# evm.net
KiCad netlist of a schematic drawn in EAGLE
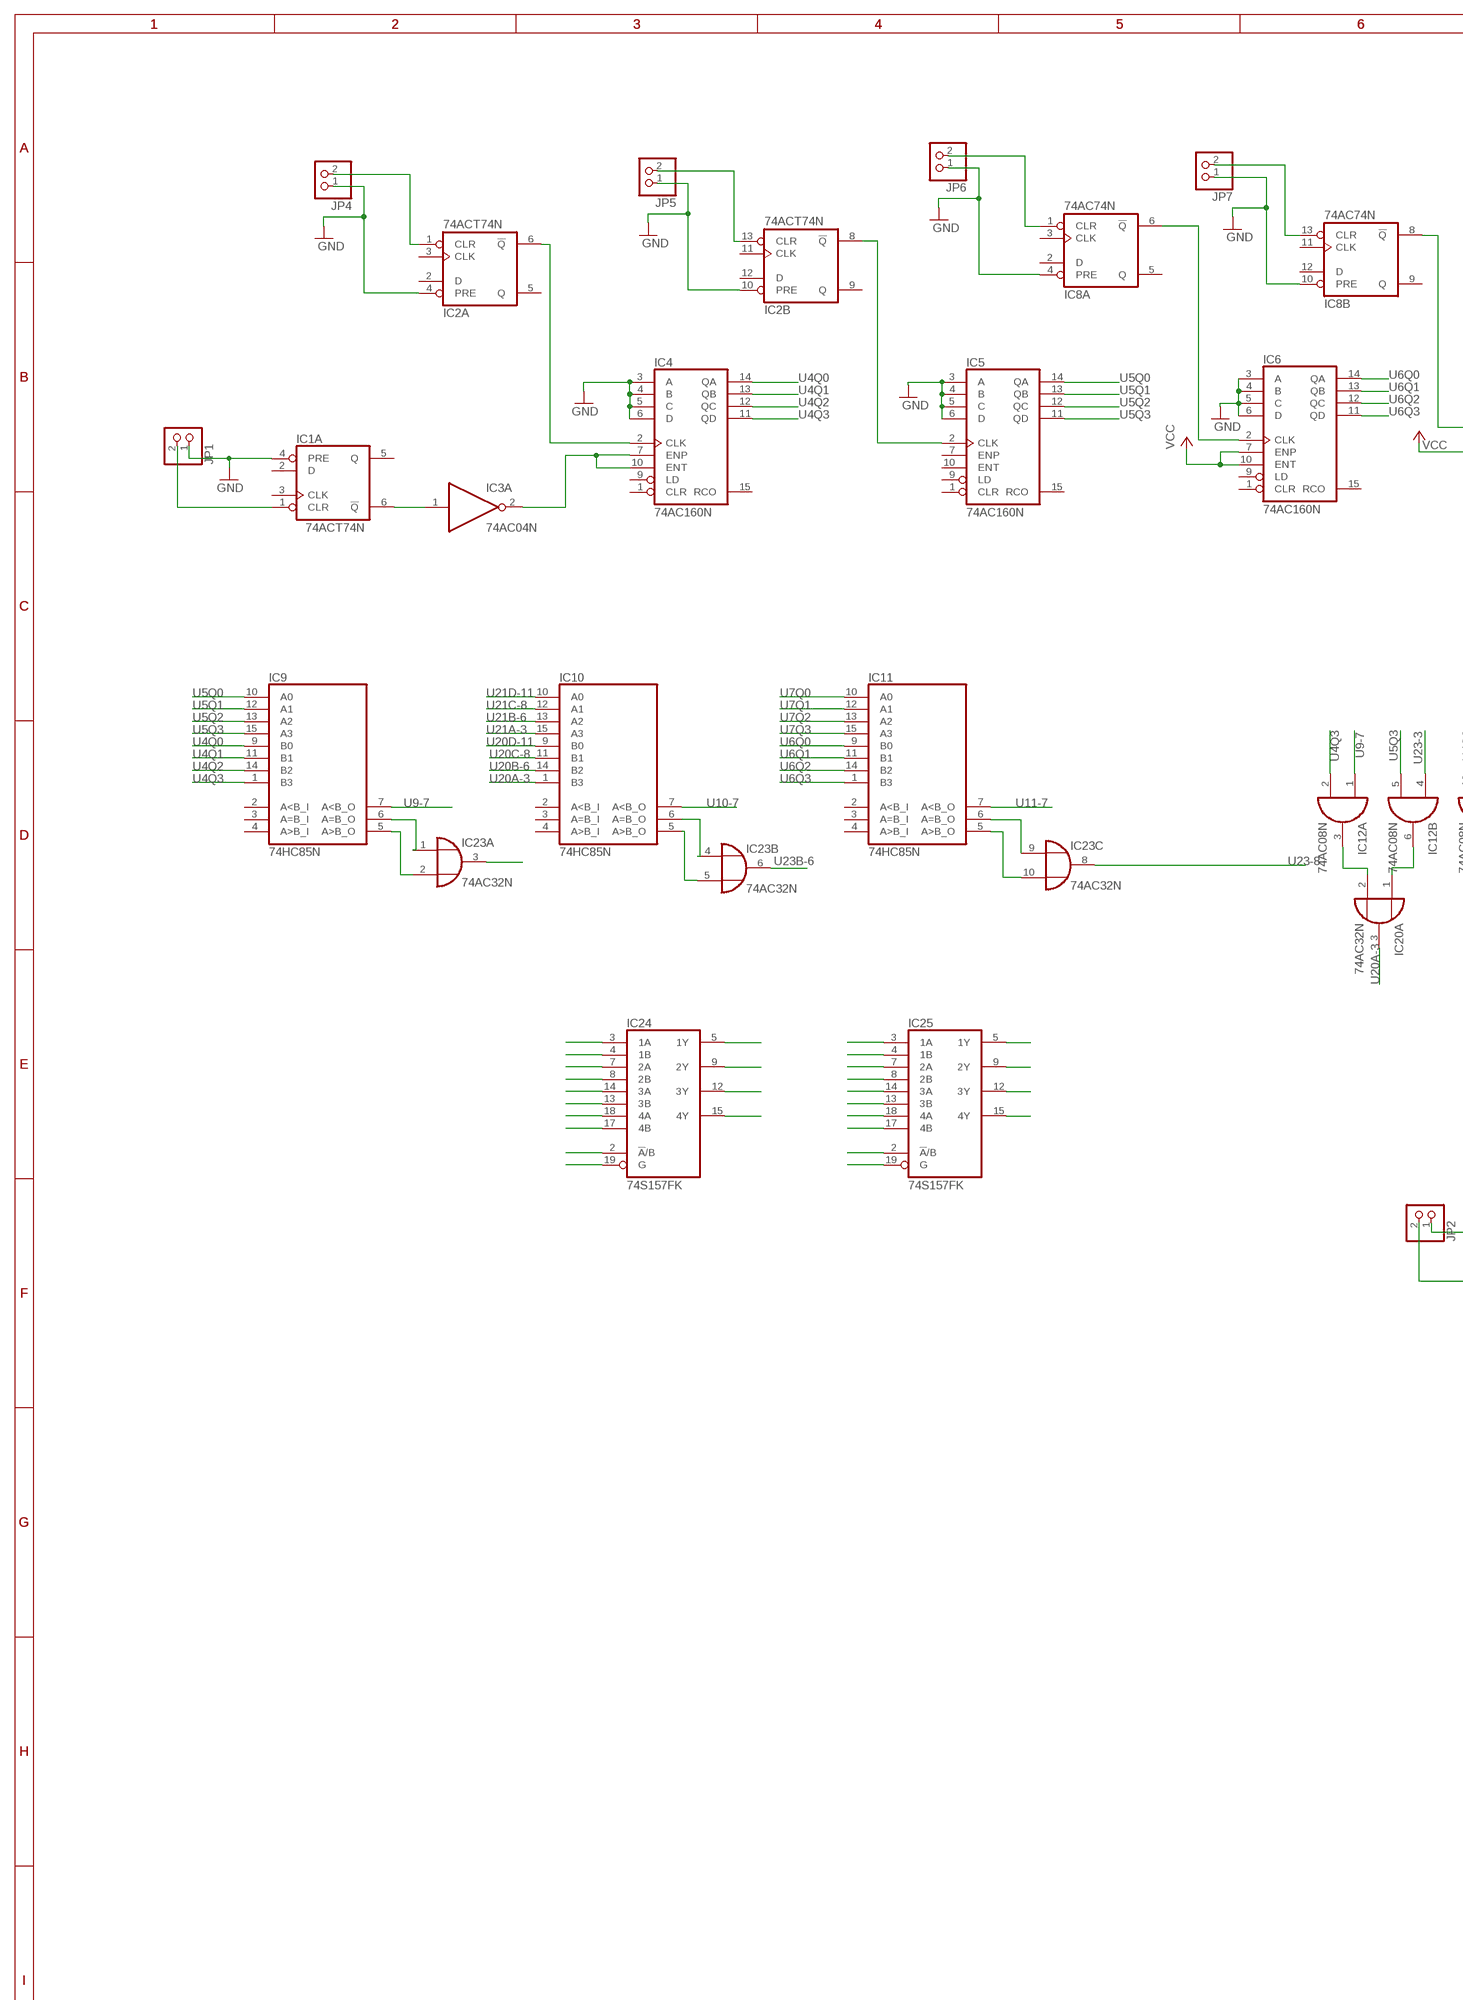
[diagram p0: schematic, sheet 1, part 1 of 2]
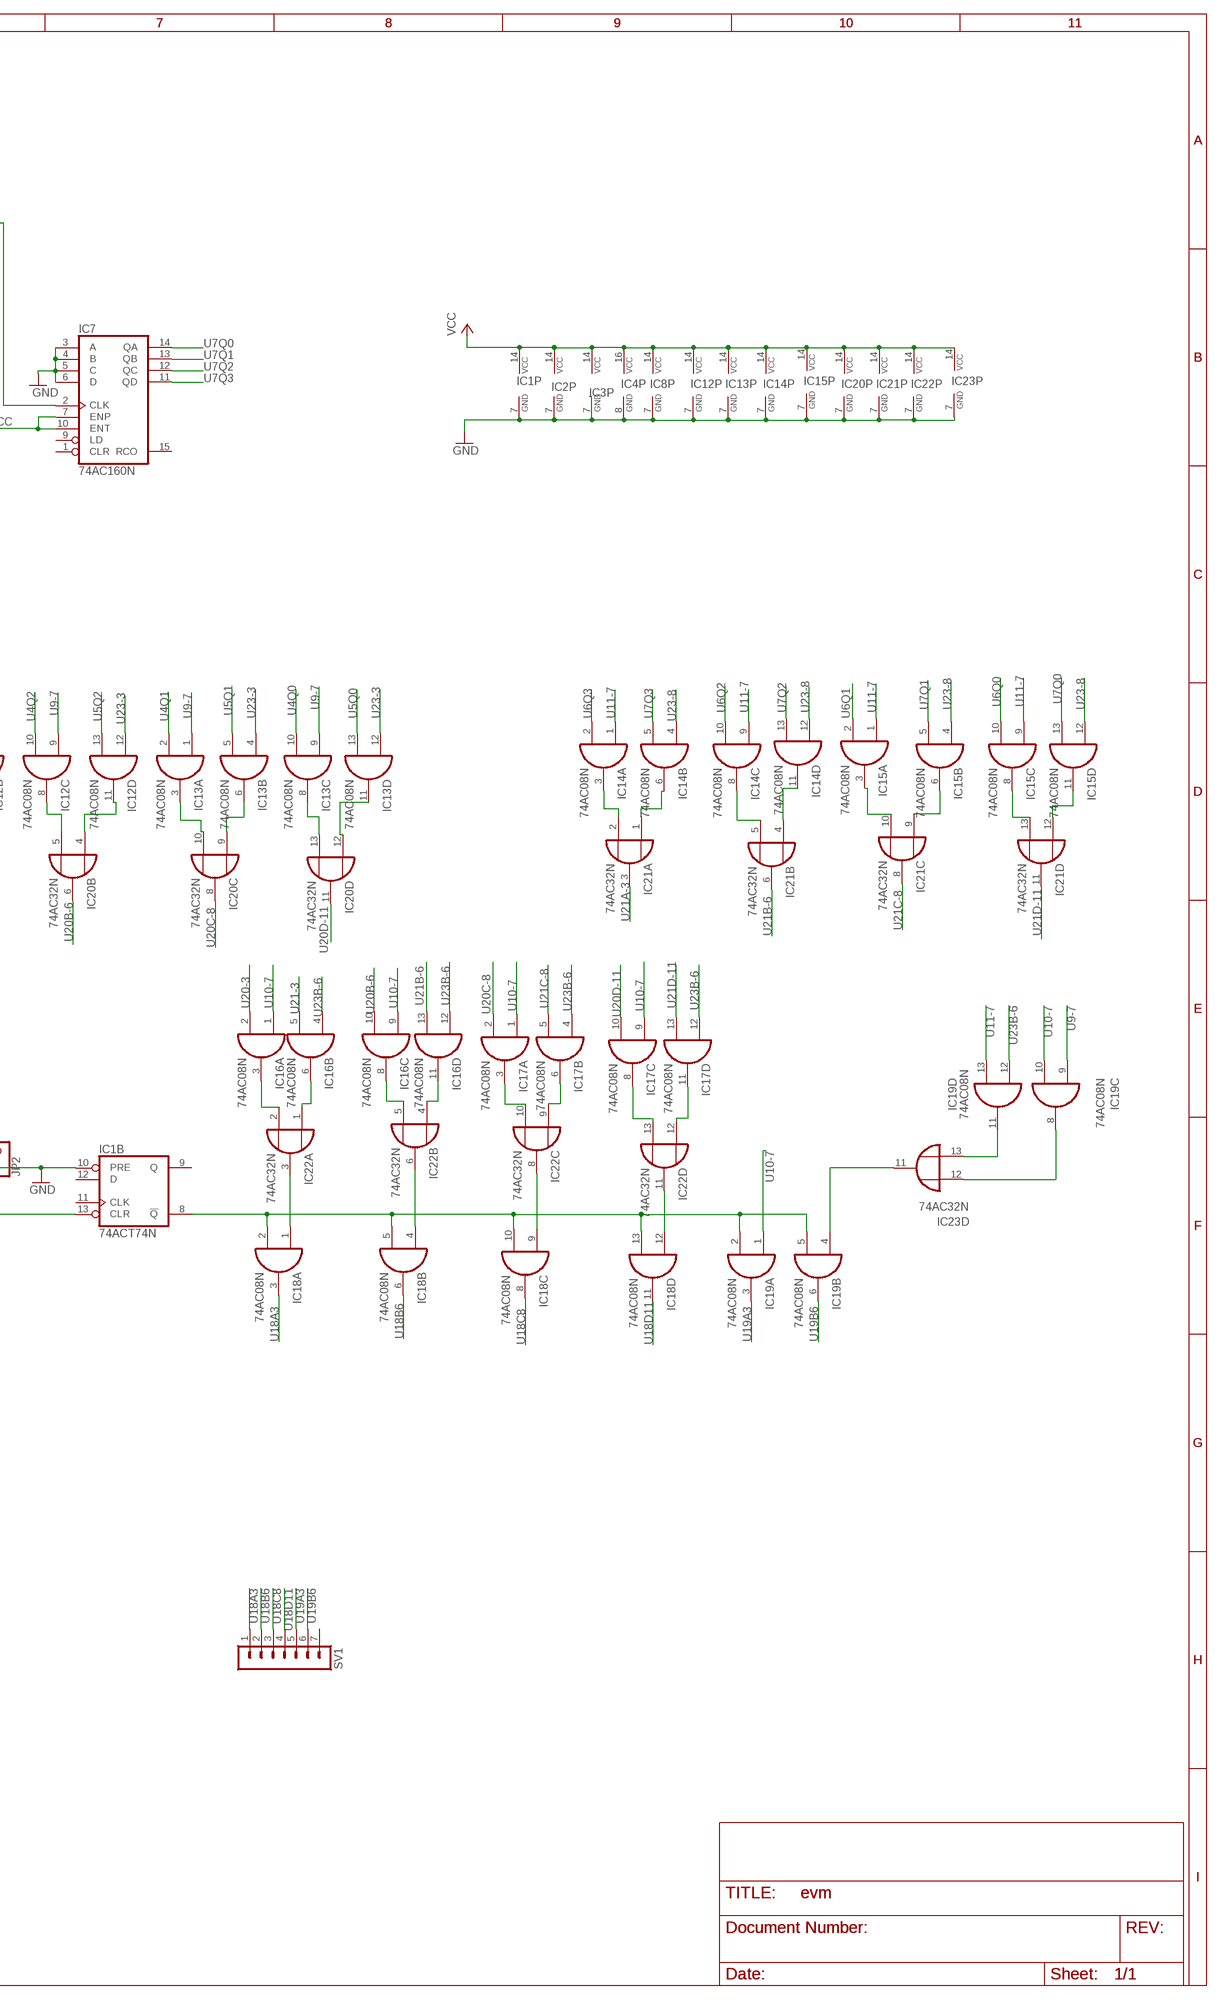
[diagram p1: schematic, sheet 1, part 2 of 2]

(export (version "E")
  (design (tool "Eeschema 10.0.6"))
  (components
    (comp (ref "IC1")
      (value "74ACT74N")
      (footprint "eagle-import:DIL14")
      (libsource (lib "eagle-import") (part "7474NACT"))
    )
    (comp (ref "IC2")
      (value "74ACT74N")
      (footprint "eagle-import:DIL14")
      (libsource (lib "eagle-import") (part "7474NACT"))
    )
    (comp (ref "IC3")
      (value "74AC04N")
      (footprint "eagle-import:DIL14")
      (libsource (lib "eagle-import") (part "7404NAC"))
    )
    (comp (ref "IC4")
      (value "74AC160N")
      (footprint "eagle-import:DIL16")
      (libsource (lib "eagle-import") (part "74160NAC"))
    )
    (comp (ref "IC5")
      (value "74AC160N")
      (footprint "eagle-import:DIL16")
      (libsource (lib "eagle-import") (part "74160NAC"))
    )
    (comp (ref "IC6")
      (value "74AC160N")
      (footprint "eagle-import:DIL16")
      (libsource (lib "eagle-import") (part "74160NAC"))
    )
    (comp (ref "IC7")
      (value "74AC160N")
      (footprint "eagle-import:DIL16")
      (libsource (lib "eagle-import") (part "74160NAC"))
    )
    (comp (ref "IC8")
      (value "74AC74N")
      (footprint "eagle-import:DIL14")
      (libsource (lib "eagle-import") (part "7474NAC"))
    )
    (comp (ref "IC9")
      (value "74HC85N")
      (footprint "eagle-import:DIL16")
      (libsource (lib "eagle-import") (part "7485NHC"))
    )
    (comp (ref "IC10")
      (value "74HC85N")
      (footprint "eagle-import:DIL16")
      (libsource (lib "eagle-import") (part "7485NHC"))
    )
    (comp (ref "IC11")
      (value "74HC85N")
      (footprint "eagle-import:DIL16")
      (libsource (lib "eagle-import") (part "7485NHC"))
    )
    (comp (ref "IC12")
      (value "74AC08N")
      (footprint "eagle-import:DIL14")
      (libsource (lib "eagle-import") (part "7408NAC"))
    )
    (comp (ref "IC13")
      (value "74AC08N")
      (footprint "eagle-import:DIL14")
      (libsource (lib "eagle-import") (part "7408NAC"))
    )
    (comp (ref "IC14")
      (value "74AC08N")
      (footprint "eagle-import:DIL14")
      (libsource (lib "eagle-import") (part "7408NAC"))
    )
    (comp (ref "IC15")
      (value "74AC08N")
      (footprint "eagle-import:DIL14")
      (libsource (lib "eagle-import") (part "7408NAC"))
    )
    (comp (ref "IC16")
      (value "74AC08N")
      (footprint "eagle-import:DIL14")
      (libsource (lib "eagle-import") (part "7408NAC"))
    )
    (comp (ref "IC17")
      (value "74AC08N")
      (footprint "eagle-import:DIL14")
      (libsource (lib "eagle-import") (part "7408NAC"))
    )
    (comp (ref "IC18")
      (value "74AC08N")
      (footprint "eagle-import:DIL14")
      (libsource (lib "eagle-import") (part "7408NAC"))
    )
    (comp (ref "IC19")
      (value "74AC08N")
      (footprint "eagle-import:DIL14")
      (libsource (lib "eagle-import") (part "7408NAC"))
    )
    (comp (ref "IC20")
      (value "74AC32N")
      (footprint "eagle-import:DIL14")
      (libsource (lib "eagle-import") (part "7432NAC"))
    )
    (comp (ref "IC21")
      (value "74AC32N")
      (footprint "eagle-import:DIL14")
      (libsource (lib "eagle-import") (part "7432NAC"))
    )
    (comp (ref "IC22")
      (value "74AC32N")
      (footprint "eagle-import:DIL14")
      (libsource (lib "eagle-import") (part "7432NAC"))
    )
    (comp (ref "IC23")
      (value "74AC32N")
      (footprint "eagle-import:DIL14")
      (libsource (lib "eagle-import") (part "7432NAC"))
    )
    (comp (ref "IC24")
      (value "74S157FK")
      (footprint "eagle-import:LCC20")
      (libsource (lib "eagle-import") (part "74157FKS"))
    )
    (comp (ref "IC25")
      (value "74S157FK")
      (footprint "eagle-import:LCC20")
      (libsource (lib "eagle-import") (part "74157FKS"))
    )
    (comp (ref "JP1")
      (value "PINHD-1X2")
      (footprint "eagle-import:1X02")
      (libsource (lib "eagle-import") (part "PINHD-1X2"))
    )
    (comp (ref "JP2")
      (value "PINHD-1X2")
      (footprint "eagle-import:1X02")
      (libsource (lib "eagle-import") (part "PINHD-1X2"))
    )
    (comp (ref "JP4")
      (value "PINHD-1X2")
      (footprint "eagle-import:1X02")
      (libsource (lib "eagle-import") (part "PINHD-1X2"))
    )
    (comp (ref "JP5")
      (value "PINHD-1X2")
      (footprint "eagle-import:1X02")
      (libsource (lib "eagle-import") (part "PINHD-1X2"))
    )
    (comp (ref "JP6")
      (value "PINHD-1X2")
      (footprint "eagle-import:1X02")
      (libsource (lib "eagle-import") (part "PINHD-1X2"))
    )
    (comp (ref "JP7")
      (value "PINHD-1X2")
      (footprint "eagle-import:1X02")
      (libsource (lib "eagle-import") (part "PINHD-1X2"))
    )
    (comp (ref "SV1")
      (value "MA07-1")
      (footprint "eagle-import:MA07-1")
      (libsource (lib "eagle-import") (part "MA07-1"))
    )
  )
  (nets
    (net (code "1") (name "/U4Q0") (class "Default")
      (node (ref "IC13") (pin "10") (pinfunction "I1_10") (pintype "input"))
      (node (ref "IC4") (pin "14") (pinfunction "QA_14") (pintype "output"))
      (node (ref "IC9") (pin "9") (pinfunction "B0_9") (pintype "input"))
    )
    (net (code "2") (name "/U4Q1") (class "Default")
      (node (ref "IC13") (pin "2") (pinfunction "I1_2") (pintype "input"))
      (node (ref "IC4") (pin "13") (pinfunction "QB_13") (pintype "output"))
      (node (ref "IC9") (pin "11") (pinfunction "B1_11") (pintype "input"))
    )
    (net (code "3") (name "/U4Q2") (class "Default")
      (node (ref "IC12") (pin "10") (pinfunction "I1_10") (pintype "input"))
      (node (ref "IC4") (pin "12") (pinfunction "QC_12") (pintype "output"))
      (node (ref "IC9") (pin "14") (pinfunction "B2_14") (pintype "input"))
    )
    (net (code "4") (name "/U4Q3") (class "Default")
      (node (ref "IC12") (pin "2") (pinfunction "I1_2") (pintype "input"))
      (node (ref "IC4") (pin "11") (pinfunction "QD_11") (pintype "output"))
      (node (ref "IC9") (pin "1") (pinfunction "B3_1") (pintype "input"))
    )
    (net (code "5") (name "/U5Q0") (class "Default")
      (node (ref "IC13") (pin "13") (pinfunction "I1_13") (pintype "input"))
      (node (ref "IC5") (pin "14") (pinfunction "QA_14") (pintype "output"))
      (node (ref "IC9") (pin "10") (pinfunction "A0_10") (pintype "input"))
    )
    (net (code "6") (name "/U5Q1") (class "Default")
      (node (ref "IC13") (pin "5") (pinfunction "I1_5") (pintype "input"))
      (node (ref "IC5") (pin "13") (pinfunction "QB_13") (pintype "output"))
      (node (ref "IC9") (pin "12") (pinfunction "A1_12") (pintype "input"))
    )
    (net (code "7") (name "/U5Q2") (class "Default")
      (node (ref "IC12") (pin "13") (pinfunction "I1_13") (pintype "input"))
      (node (ref "IC5") (pin "12") (pinfunction "QC_12") (pintype "output"))
      (node (ref "IC9") (pin "13") (pinfunction "A2_13") (pintype "input"))
    )
    (net (code "8") (name "/U5Q3") (class "Default")
      (node (ref "IC12") (pin "5") (pinfunction "I1_5") (pintype "input"))
      (node (ref "IC5") (pin "11") (pinfunction "QD_11") (pintype "output"))
      (node (ref "IC9") (pin "15") (pinfunction "A3_15") (pintype "input"))
    )
    (net (code "9") (name "/U6Q0") (class "Default")
      (node (ref "IC11") (pin "9") (pinfunction "B0_9") (pintype "input"))
      (node (ref "IC15") (pin "10") (pinfunction "I1_10") (pintype "input"))
      (node (ref "IC6") (pin "14") (pinfunction "QA_14") (pintype "output"))
    )
    (net (code "10") (name "/U6Q1") (class "Default")
      (node (ref "IC11") (pin "11") (pinfunction "B1_11") (pintype "input"))
      (node (ref "IC15") (pin "2") (pinfunction "I1_2") (pintype "input"))
      (node (ref "IC6") (pin "13") (pinfunction "QB_13") (pintype "output"))
    )
    (net (code "11") (name "/U6Q2") (class "Default")
      (node (ref "IC11") (pin "14") (pinfunction "B2_14") (pintype "input"))
      (node (ref "IC14") (pin "10") (pinfunction "I1_10") (pintype "input"))
      (node (ref "IC6") (pin "12") (pinfunction "QC_12") (pintype "output"))
    )
    (net (code "12") (name "/U6Q3") (class "Default")
      (node (ref "IC11") (pin "1") (pinfunction "B3_1") (pintype "input"))
      (node (ref "IC14") (pin "2") (pinfunction "I1_2") (pintype "input"))
      (node (ref "IC6") (pin "11") (pinfunction "QD_11") (pintype "output"))
    )
    (net (code "13") (name "/U7Q0") (class "Default")
      (node (ref "IC11") (pin "10") (pinfunction "A0_10") (pintype "input"))
      (node (ref "IC15") (pin "13") (pinfunction "I1_13") (pintype "input"))
      (node (ref "IC7") (pin "14") (pinfunction "QA_14") (pintype "output"))
    )
    (net (code "14") (name "/U7Q1") (class "Default")
      (node (ref "IC11") (pin "12") (pinfunction "A1_12") (pintype "input"))
      (node (ref "IC15") (pin "5") (pinfunction "I1_5") (pintype "input"))
      (node (ref "IC7") (pin "13") (pinfunction "QB_13") (pintype "output"))
    )
    (net (code "15") (name "/U7Q2") (class "Default")
      (node (ref "IC11") (pin "13") (pinfunction "A2_13") (pintype "input"))
      (node (ref "IC14") (pin "13") (pinfunction "I1_13") (pintype "input"))
      (node (ref "IC7") (pin "12") (pinfunction "QC_12") (pintype "output"))
    )
    (net (code "16") (name "/U7Q3") (class "Default")
      (node (ref "IC11") (pin "15") (pinfunction "A3_15") (pintype "input"))
      (node (ref "IC14") (pin "5") (pinfunction "I1_5") (pintype "input"))
      (node (ref "IC7") (pin "11") (pinfunction "QD_11") (pintype "output"))
    )
    (net (code "17") (name "/U9-7") (class "Default")
      (node (ref "IC12") (pin "1") (pinfunction "I0_1") (pintype "input"))
      (node (ref "IC12") (pin "9") (pinfunction "I0_9") (pintype "input"))
      (node (ref "IC13") (pin "1") (pinfunction "I0_1") (pintype "input"))
      (node (ref "IC13") (pin "9") (pinfunction "I0_9") (pintype "input"))
      (node (ref "IC19") (pin "9") (pinfunction "I0_9") (pintype "input"))
      (node (ref "IC9") (pin "7") (pinfunction "A<B_O_7") (pintype "output"))
    )
    (net (code "18") (name "/U10-7") (class "Default")
      (node (ref "IC10") (pin "7") (pinfunction "A<B_O_7") (pintype "output"))
      (node (ref "IC16") (pin "1") (pinfunction "I0_1") (pintype "input"))
      (node (ref "IC16") (pin "9") (pinfunction "I0_9") (pintype "input"))
      (node (ref "IC17") (pin "1") (pinfunction "I0_1") (pintype "input"))
      (node (ref "IC17") (pin "9") (pinfunction "I0_9") (pintype "input"))
      (node (ref "IC19") (pin "1") (pinfunction "I0_1") (pintype "input"))
      (node (ref "IC19") (pin "10") (pinfunction "I1_10") (pintype "input"))
    )
    (net (code "19") (name "/U11-7") (class "Default")
      (node (ref "IC11") (pin "7") (pinfunction "A<B_O_7") (pintype "output"))
      (node (ref "IC14") (pin "1") (pinfunction "I0_1") (pintype "input"))
      (node (ref "IC14") (pin "9") (pinfunction "I0_9") (pintype "input"))
      (node (ref "IC15") (pin "1") (pinfunction "I0_1") (pintype "input"))
      (node (ref "IC15") (pin "9") (pinfunction "I0_9") (pintype "input"))
      (node (ref "IC19") (pin "13") (pinfunction "I1_13") (pintype "input"))
    )
    (net (code "20") (name "/U18A3") (class "Default")
      (node (ref "IC18") (pin "3") (pinfunction "O_3") (pintype "output"))
      (node (ref "SV1") (pin "1") (pinfunction "1_1") (pintype "passive"))
    )
    (net (code "21") (name "/U18B6") (class "Default")
      (node (ref "IC18") (pin "6") (pinfunction "O_6") (pintype "output"))
      (node (ref "SV1") (pin "2") (pinfunction "2_2") (pintype "passive"))
    )
    (net (code "22") (name "/U18C8") (class "Default")
      (node (ref "IC18") (pin "8") (pinfunction "O_8") (pintype "output"))
      (node (ref "SV1") (pin "3") (pinfunction "3_3") (pintype "passive"))
    )
    (net (code "23") (name "/U18D11") (class "Default")
      (node (ref "IC18") (pin "11") (pinfunction "O_11") (pintype "output"))
      (node (ref "SV1") (pin "4") (pinfunction "4_4") (pintype "passive"))
    )
    (net (code "24") (name "/U19A3") (class "Default")
      (node (ref "IC19") (pin "3") (pinfunction "O_3") (pintype "output"))
      (node (ref "SV1") (pin "5") (pinfunction "5_5") (pintype "passive"))
    )
    (net (code "25") (name "/U19B6") (class "Default")
      (node (ref "IC19") (pin "6") (pinfunction "O_6") (pintype "output"))
      (node (ref "SV1") (pin "6") (pinfunction "6_6") (pintype "passive"))
    )
    (net (code "26") (name "/U20-3") (class "Default")
      (node (ref "IC16") (pin "2") (pinfunction "I1_2") (pintype "input"))
    )
    (net (code "27") (name "/U20A-3") (class "Default")
      (node (ref "IC10") (pin "1") (pinfunction "B3_1") (pintype "input"))
      (node (ref "IC20") (pin "3") (pinfunction "O_3") (pintype "output"))
    )
    (net (code "28") (name "/U20B-6") (class "Default")
      (node (ref "IC10") (pin "14") (pinfunction "B2_14") (pintype "input"))
      (node (ref "IC16") (pin "10") (pinfunction "I1_10") (pintype "input"))
      (node (ref "IC20") (pin "6") (pinfunction "O_6") (pintype "output"))
    )
    (net (code "29") (name "/U20C-8") (class "Default")
      (node (ref "IC10") (pin "11") (pinfunction "B1_11") (pintype "input"))
      (node (ref "IC17") (pin "2") (pinfunction "I1_2") (pintype "input"))
      (node (ref "IC20") (pin "8") (pinfunction "O_8") (pintype "output"))
    )
    (net (code "30") (name "/U20D-11") (class "Default")
      (node (ref "IC10") (pin "9") (pinfunction "B0_9") (pintype "input"))
      (node (ref "IC17") (pin "10") (pinfunction "I1_10") (pintype "input"))
      (node (ref "IC20") (pin "11") (pinfunction "O_11") (pintype "output"))
    )
    (net (code "31") (name "/U21-3") (class "Default")
      (node (ref "IC16") (pin "5") (pinfunction "I1_5") (pintype "input"))
    )
    (net (code "32") (name "/U21A-3") (class "Default")
      (node (ref "IC10") (pin "15") (pinfunction "A3_15") (pintype "input"))
      (node (ref "IC21") (pin "3") (pinfunction "O_3") (pintype "output"))
    )
    (net (code "33") (name "/U21B-6") (class "Default")
      (node (ref "IC10") (pin "13") (pinfunction "A2_13") (pintype "input"))
      (node (ref "IC16") (pin "13") (pinfunction "I1_13") (pintype "input"))
      (node (ref "IC21") (pin "6") (pinfunction "O_6") (pintype "output"))
    )
    (net (code "34") (name "/U21C-8") (class "Default")
      (node (ref "IC10") (pin "12") (pinfunction "A1_12") (pintype "input"))
      (node (ref "IC17") (pin "5") (pinfunction "I1_5") (pintype "input"))
      (node (ref "IC21") (pin "8") (pinfunction "O_8") (pintype "output"))
    )
    (net (code "35") (name "/U21D-11") (class "Default")
      (node (ref "IC10") (pin "10") (pinfunction "A0_10") (pintype "input"))
      (node (ref "IC17") (pin "13") (pinfunction "I1_13") (pintype "input"))
      (node (ref "IC21") (pin "11") (pinfunction "O_11") (pintype "output"))
    )
    (net (code "36") (name "/U23-3") (class "Default")
      (node (ref "IC12") (pin "12") (pinfunction "I0_12") (pintype "input"))
      (node (ref "IC12") (pin "4") (pinfunction "I0_4") (pintype "input"))
      (node (ref "IC13") (pin "12") (pinfunction "I0_12") (pintype "input"))
      (node (ref "IC13") (pin "4") (pinfunction "I0_4") (pintype "input"))
    )
    (net (code "37") (name "/U23-8") (class "Default")
      (node (ref "IC14") (pin "12") (pinfunction "I0_12") (pintype "input"))
      (node (ref "IC14") (pin "4") (pinfunction "I0_4") (pintype "input"))
      (node (ref "IC15") (pin "12") (pinfunction "I0_12") (pintype "input"))
      (node (ref "IC15") (pin "4") (pinfunction "I0_4") (pintype "input"))
      (node (ref "IC23") (pin "8") (pinfunction "O_8") (pintype "output"))
    )
    (net (code "38") (name "/U23B-6") (class "Default")
      (node (ref "IC16") (pin "12") (pinfunction "I0_12") (pintype "input"))
      (node (ref "IC16") (pin "4") (pinfunction "I0_4") (pintype "input"))
      (node (ref "IC17") (pin "12") (pinfunction "I0_12") (pintype "input"))
      (node (ref "IC17") (pin "4") (pinfunction "I0_4") (pintype "input"))
      (node (ref "IC19") (pin "12") (pinfunction "I0_12") (pintype "input"))
      (node (ref "IC23") (pin "6") (pinfunction "O_6") (pintype "output"))
    )
    (net (code "39") (name "GND") (class "Default")
      (node (ref "IC1") (pin "10") (pinfunction "PRE_10") (pintype "input"))
      (node (ref "IC1") (pin "4") (pinfunction "PRE_4") (pintype "input"))
      (node (ref "IC1") (pin "7") (pinfunction "GND_7") (pintype "power_in"))
      (node (ref "IC12") (pin "7") (pinfunction "GND_7") (pintype "power_in"))
      (node (ref "IC13") (pin "7") (pinfunction "GND_7") (pintype "power_in"))
      (node (ref "IC14") (pin "7") (pinfunction "GND_7") (pintype "power_in"))
      (node (ref "IC15") (pin "7") (pinfunction "GND_7") (pintype "power_in"))
      (node (ref "IC2") (pin "10") (pinfunction "PRE_10") (pintype "input"))
      (node (ref "IC2") (pin "4") (pinfunction "PRE_4") (pintype "input"))
      (node (ref "IC2") (pin "7") (pinfunction "GND_7") (pintype "power_in"))
      (node (ref "IC20") (pin "7") (pinfunction "GND_7") (pintype "power_in"))
      (node (ref "IC21") (pin "7") (pinfunction "GND_7") (pintype "power_in"))
      (node (ref "IC22") (pin "7") (pinfunction "GND_7") (pintype "power_in"))
      (node (ref "IC23") (pin "7") (pinfunction "GND_7") (pintype "power_in"))
      (node (ref "IC3") (pin "7") (pinfunction "GND_7") (pintype "power_in"))
      (node (ref "IC4") (pin "3") (pinfunction "A_3") (pintype "input"))
      (node (ref "IC4") (pin "4") (pinfunction "B_4") (pintype "input"))
      (node (ref "IC4") (pin "5") (pinfunction "C_5") (pintype "input"))
      (node (ref "IC4") (pin "6") (pinfunction "D_6") (pintype "input"))
      (node (ref "IC4") (pin "8") (pinfunction "GND_8") (pintype "power_in"))
      (node (ref "IC5") (pin "3") (pinfunction "A_3") (pintype "input"))
      (node (ref "IC5") (pin "4") (pinfunction "B_4") (pintype "input"))
      (node (ref "IC5") (pin "5") (pinfunction "C_5") (pintype "input"))
      (node (ref "IC5") (pin "6") (pinfunction "D_6") (pintype "input"))
      (node (ref "IC6") (pin "3") (pinfunction "A_3") (pintype "input"))
      (node (ref "IC6") (pin "4") (pinfunction "B_4") (pintype "input"))
      (node (ref "IC6") (pin "5") (pinfunction "C_5") (pintype "input"))
      (node (ref "IC6") (pin "6") (pinfunction "D_6") (pintype "input"))
      (node (ref "IC7") (pin "3") (pinfunction "A_3") (pintype "input"))
      (node (ref "IC7") (pin "4") (pinfunction "B_4") (pintype "input"))
      (node (ref "IC7") (pin "5") (pinfunction "C_5") (pintype "input"))
      (node (ref "IC7") (pin "6") (pinfunction "D_6") (pintype "input"))
      (node (ref "IC8") (pin "10") (pinfunction "PRE_10") (pintype "input"))
      (node (ref "IC8") (pin "4") (pinfunction "PRE_4") (pintype "input"))
      (node (ref "IC8") (pin "7") (pinfunction "GND_7") (pintype "power_in"))
      (node (ref "JP1") (pin "1") (pinfunction "1_1") (pintype "passive"))
      (node (ref "JP2") (pin "1") (pinfunction "1_1") (pintype "passive"))
      (node (ref "JP4") (pin "1") (pinfunction "1_1") (pintype "passive"))
      (node (ref "JP5") (pin "1") (pinfunction "1_1") (pintype "passive"))
      (node (ref "JP6") (pin "1") (pinfunction "1_1") (pintype "passive"))
      (node (ref "JP7") (pin "1") (pinfunction "1_1") (pintype "passive"))
    )
    (net (code "40") (name "Net-(IC1A-CLR)") (class "Default")
      (node (ref "IC1") (pin "1") (pinfunction "CLR_1") (pintype "input"))
      (node (ref "JP1") (pin "2") (pinfunction "2_2") (pintype "passive"))
    )
    (net (code "41") (name "Net-(IC1A-~{Q})") (class "Default")
      (node (ref "IC1") (pin "6") (pinfunction "~{Q}_6") (pintype "output"))
      (node (ref "IC3") (pin "1") (pinfunction "I_1") (pintype "input"))
    )
    (net (code "42") (name "Net-(IC1B-CLR)") (class "Default")
      (node (ref "IC1") (pin "13") (pinfunction "CLR_13") (pintype "input"))
      (node (ref "JP2") (pin "2") (pinfunction "2_2") (pintype "passive"))
    )
    (net (code "43") (name "Net-(IC2A-CLR)") (class "Default")
      (node (ref "IC2") (pin "1") (pinfunction "CLR_1") (pintype "input"))
      (node (ref "JP4") (pin "2") (pinfunction "2_2") (pintype "passive"))
    )
    (net (code "44") (name "Net-(IC2A-~{Q})") (class "Default")
      (node (ref "IC2") (pin "6") (pinfunction "~{Q}_6") (pintype "output"))
      (node (ref "IC4") (pin "2") (pinfunction "CLK_2") (pintype "input"))
    )
    (net (code "45") (name "Net-(IC2B-CLR)") (class "Default")
      (node (ref "IC2") (pin "13") (pinfunction "CLR_13") (pintype "input"))
      (node (ref "JP5") (pin "2") (pinfunction "2_2") (pintype "passive"))
    )
    (net (code "46") (name "Net-(IC2B-~{Q})") (class "Default")
      (node (ref "IC2") (pin "8") (pinfunction "~{Q}_8") (pintype "output"))
      (node (ref "IC5") (pin "2") (pinfunction "CLK_2") (pintype "input"))
    )
    (net (code "47") (name "Net-(IC3A-O)") (class "Default")
      (node (ref "IC3") (pin "2") (pinfunction "O_2") (pintype "output"))
      (node (ref "IC4") (pin "10") (pinfunction "ENT_10") (pintype "input"))
      (node (ref "IC4") (pin "7") (pinfunction "ENP_7") (pintype "input"))
    )
    (net (code "48") (name "Net-(IC6A-CLK)") (class "Default")
      (node (ref "IC6") (pin "2") (pinfunction "CLK_2") (pintype "input"))
      (node (ref "IC8") (pin "6") (pinfunction "~{Q}_6") (pintype "output"))
    )
    (net (code "49") (name "Net-(IC7A-CLK)") (class "Default")
      (node (ref "IC7") (pin "2") (pinfunction "CLK_2") (pintype "input"))
      (node (ref "IC8") (pin "8") (pinfunction "~{Q}_8") (pintype "output"))
    )
    (net (code "50") (name "Net-(IC7A-ENP)") (class "Default")
      (node (ref "IC7") (pin "10") (pinfunction "ENT_10") (pintype "input"))
      (node (ref "IC7") (pin "7") (pinfunction "ENP_7") (pintype "input"))
    )
    (net (code "51") (name "Net-(IC8A-CLR)") (class "Default")
      (node (ref "IC8") (pin "1") (pinfunction "CLR_1") (pintype "input"))
      (node (ref "JP6") (pin "2") (pinfunction "2_2") (pintype "passive"))
    )
    (net (code "52") (name "Net-(IC8B-CLR)") (class "Default")
      (node (ref "IC8") (pin "13") (pinfunction "CLR_13") (pintype "input"))
      (node (ref "JP7") (pin "2") (pinfunction "2_2") (pintype "passive"))
    )
    (net (code "53") (name "Net-(IC10A-A=B_O)") (class "Default")
      (node (ref "IC10") (pin "6") (pinfunction "A=B_O_6") (pintype "output"))
      (node (ref "IC23") (pin "4") (pinfunction "I0_4") (pintype "input"))
    )
    (net (code "54") (name "Net-(IC10A-A>B_O)") (class "Default")
      (node (ref "IC10") (pin "5") (pinfunction "A>B_O_5") (pintype "output"))
      (node (ref "IC23") (pin "5") (pinfunction "I1_5") (pintype "input"))
    )
    (net (code "55") (name "Net-(IC11A-A=B_O)") (class "Default")
      (node (ref "IC11") (pin "6") (pinfunction "A=B_O_6") (pintype "output"))
      (node (ref "IC23") (pin "9") (pinfunction "I0_9") (pintype "input"))
    )
    (net (code "56") (name "Net-(IC11A-A>B_O)") (class "Default")
      (node (ref "IC11") (pin "5") (pinfunction "A>B_O_5") (pintype "output"))
      (node (ref "IC23") (pin "10") (pinfunction "I1_10") (pintype "input"))
    )
    (net (code "57") (name "Net-(IC12A-O)") (class "Default")
      (node (ref "IC12") (pin "3") (pinfunction "O_3") (pintype "output"))
      (node (ref "IC20") (pin "2") (pinfunction "I1_2") (pintype "input"))
    )
    (net (code "58") (name "Net-(IC12B-O)") (class "Default")
      (node (ref "IC12") (pin "6") (pinfunction "O_6") (pintype "output"))
      (node (ref "IC20") (pin "1") (pinfunction "I0_1") (pintype "input"))
    )
    (net (code "59") (name "Net-(IC12C-O)") (class "Default")
      (node (ref "IC12") (pin "8") (pinfunction "O_8") (pintype "output"))
      (node (ref "IC20") (pin "5") (pinfunction "I1_5") (pintype "input"))
    )
    (net (code "60") (name "Net-(IC12D-O)") (class "Default")
      (node (ref "IC12") (pin "11") (pinfunction "O_11") (pintype "output"))
      (node (ref "IC20") (pin "4") (pinfunction "I0_4") (pintype "input"))
    )
    (net (code "61") (name "Net-(IC13A-O)") (class "Default")
      (node (ref "IC13") (pin "3") (pinfunction "O_3") (pintype "output"))
      (node (ref "IC20") (pin "10") (pinfunction "I1_10") (pintype "input"))
    )
    (net (code "62") (name "Net-(IC13B-O)") (class "Default")
      (node (ref "IC13") (pin "6") (pinfunction "O_6") (pintype "output"))
      (node (ref "IC20") (pin "9") (pinfunction "I0_9") (pintype "input"))
    )
    (net (code "63") (name "Net-(IC13C-O)") (class "Default")
      (node (ref "IC13") (pin "8") (pinfunction "O_8") (pintype "output"))
      (node (ref "IC20") (pin "13") (pinfunction "I1_13") (pintype "input"))
    )
    (net (code "64") (name "Net-(IC13D-O)") (class "Default")
      (node (ref "IC13") (pin "11") (pinfunction "O_11") (pintype "output"))
      (node (ref "IC20") (pin "12") (pinfunction "I0_12") (pintype "input"))
    )
    (net (code "65") (name "Net-(IC14A-O)") (class "Default")
      (node (ref "IC14") (pin "3") (pinfunction "O_3") (pintype "output"))
      (node (ref "IC21") (pin "2") (pinfunction "I1_2") (pintype "input"))
    )
    (net (code "66") (name "Net-(IC14B-O)") (class "Default")
      (node (ref "IC14") (pin "6") (pinfunction "O_6") (pintype "output"))
      (node (ref "IC21") (pin "1") (pinfunction "I0_1") (pintype "input"))
    )
    (net (code "67") (name "Net-(IC14C-O)") (class "Default")
      (node (ref "IC14") (pin "8") (pinfunction "O_8") (pintype "output"))
      (node (ref "IC21") (pin "5") (pinfunction "I1_5") (pintype "input"))
    )
    (net (code "68") (name "Net-(IC14D-O)") (class "Default")
      (node (ref "IC14") (pin "11") (pinfunction "O_11") (pintype "output"))
      (node (ref "IC21") (pin "4") (pinfunction "I0_4") (pintype "input"))
    )
    (net (code "69") (name "Net-(IC15A-O)") (class "Default")
      (node (ref "IC15") (pin "3") (pinfunction "O_3") (pintype "output"))
      (node (ref "IC21") (pin "10") (pinfunction "I1_10") (pintype "input"))
    )
    (net (code "70") (name "Net-(IC15B-O)") (class "Default")
      (node (ref "IC15") (pin "6") (pinfunction "O_6") (pintype "output"))
      (node (ref "IC21") (pin "9") (pinfunction "I0_9") (pintype "input"))
    )
    (net (code "71") (name "Net-(IC15C-O)") (class "Default")
      (node (ref "IC15") (pin "8") (pinfunction "O_8") (pintype "output"))
      (node (ref "IC21") (pin "13") (pinfunction "I1_13") (pintype "input"))
    )
    (net (code "72") (name "Net-(IC15D-O)") (class "Default")
      (node (ref "IC15") (pin "11") (pinfunction "O_11") (pintype "output"))
      (node (ref "IC21") (pin "12") (pinfunction "I0_12") (pintype "input"))
    )
    (net (code "73") (name "Net-(IC16A-O)") (class "Default")
      (node (ref "IC16") (pin "3") (pinfunction "O_3") (pintype "output"))
      (node (ref "IC22") (pin "2") (pinfunction "I1_2") (pintype "input"))
    )
    (net (code "74") (name "Net-(IC16B-O)") (class "Default")
      (node (ref "IC16") (pin "6") (pinfunction "O_6") (pintype "output"))
      (node (ref "IC22") (pin "1") (pinfunction "I0_1") (pintype "input"))
    )
    (net (code "75") (name "Net-(IC16C-O)") (class "Default")
      (node (ref "IC16") (pin "8") (pinfunction "O_8") (pintype "output"))
      (node (ref "IC22") (pin "5") (pinfunction "I1_5") (pintype "input"))
    )
    (net (code "76") (name "Net-(IC16D-O)") (class "Default")
      (node (ref "IC16") (pin "11") (pinfunction "O_11") (pintype "output"))
      (node (ref "IC22") (pin "4") (pinfunction "I0_4") (pintype "input"))
    )
    (net (code "77") (name "Net-(IC17A-O)") (class "Default")
      (node (ref "IC17") (pin "3") (pinfunction "O_3") (pintype "output"))
      (node (ref "IC22") (pin "10") (pinfunction "I1_10") (pintype "input"))
    )
    (net (code "78") (name "Net-(IC17B-O)") (class "Default")
      (node (ref "IC17") (pin "6") (pinfunction "O_6") (pintype "output"))
      (node (ref "IC22") (pin "9") (pinfunction "I0_9") (pintype "input"))
    )
    (net (code "79") (name "Net-(IC17C-O)") (class "Default")
      (node (ref "IC17") (pin "8") (pinfunction "O_8") (pintype "output"))
      (node (ref "IC22") (pin "13") (pinfunction "I1_13") (pintype "input"))
    )
    (net (code "80") (name "Net-(IC17D-O)") (class "Default")
      (node (ref "IC17") (pin "11") (pinfunction "O_11") (pintype "output"))
      (node (ref "IC22") (pin "12") (pinfunction "I0_12") (pintype "input"))
    )
    (net (code "81") (name "Net-(IC18A-I0)") (class "Default")
      (node (ref "IC18") (pin "1") (pinfunction "I0_1") (pintype "input"))
      (node (ref "IC22") (pin "3") (pinfunction "O_3") (pintype "output"))
    )
    (net (code "82") (name "Net-(IC18A-I1)") (class "Default")
      (node (ref "IC1") (pin "8") (pinfunction "~{Q}_8") (pintype "output"))
      (node (ref "IC18") (pin "10") (pinfunction "I1_10") (pintype "input"))
      (node (ref "IC18") (pin "13") (pinfunction "I1_13") (pintype "input"))
      (node (ref "IC18") (pin "2") (pinfunction "I1_2") (pintype "input"))
      (node (ref "IC18") (pin "5") (pinfunction "I1_5") (pintype "input"))
      (node (ref "IC19") (pin "2") (pinfunction "I1_2") (pintype "input"))
      (node (ref "IC19") (pin "5") (pinfunction "I1_5") (pintype "input"))
    )
    (net (code "83") (name "Net-(IC18B-I0)") (class "Default")
      (node (ref "IC18") (pin "4") (pinfunction "I0_4") (pintype "input"))
      (node (ref "IC22") (pin "6") (pinfunction "O_6") (pintype "output"))
    )
    (net (code "84") (name "Net-(IC18C-I0)") (class "Default")
      (node (ref "IC18") (pin "9") (pinfunction "I0_9") (pintype "input"))
      (node (ref "IC22") (pin "8") (pinfunction "O_8") (pintype "output"))
    )
    (net (code "85") (name "Net-(IC18D-I0)") (class "Default")
      (node (ref "IC18") (pin "12") (pinfunction "I0_12") (pintype "input"))
      (node (ref "IC22") (pin "11") (pinfunction "O_11") (pintype "output"))
    )
    (net (code "86") (name "Net-(IC19B-I0)") (class "Default")
      (node (ref "IC19") (pin "4") (pinfunction "I0_4") (pintype "input"))
      (node (ref "IC23") (pin "11") (pinfunction "O_11") (pintype "output"))
    )
    (net (code "87") (name "Net-(IC19C-O)") (class "Default")
      (node (ref "IC19") (pin "8") (pinfunction "O_8") (pintype "output"))
      (node (ref "IC23") (pin "12") (pinfunction "I0_12") (pintype "input"))
    )
    (net (code "88") (name "Net-(IC19D-O)") (class "Default")
      (node (ref "IC19") (pin "11") (pinfunction "O_11") (pintype "output"))
      (node (ref "IC23") (pin "13") (pinfunction "I1_13") (pintype "input"))
    )
    (net (code "89") (name "Net-(IC23A-I0)") (class "Default")
      (node (ref "IC23") (pin "1") (pinfunction "I0_1") (pintype "input"))
      (node (ref "IC9") (pin "6") (pinfunction "A=B_O_6") (pintype "output"))
    )
    (net (code "90") (name "Net-(IC23A-I1)") (class "Default")
      (node (ref "IC23") (pin "2") (pinfunction "I1_2") (pintype "input"))
      (node (ref "IC9") (pin "5") (pinfunction "A>B_O_5") (pintype "output"))
    )
    (net (code "91") (name "VCC") (class "Default")
      (node (ref "IC1") (pin "14") (pinfunction "VCC_14") (pintype "power_in"))
      (node (ref "IC12") (pin "14") (pinfunction "VCC_14") (pintype "power_in"))
      (node (ref "IC13") (pin "14") (pinfunction "VCC_14") (pintype "power_in"))
      (node (ref "IC14") (pin "14") (pinfunction "VCC_14") (pintype "power_in"))
      (node (ref "IC15") (pin "14") (pinfunction "VCC_14") (pintype "power_in"))
      (node (ref "IC2") (pin "14") (pinfunction "VCC_14") (pintype "power_in"))
      (node (ref "IC20") (pin "14") (pinfunction "VCC_14") (pintype "power_in"))
      (node (ref "IC21") (pin "14") (pinfunction "VCC_14") (pintype "power_in"))
      (node (ref "IC22") (pin "14") (pinfunction "VCC_14") (pintype "power_in"))
      (node (ref "IC23") (pin "14") (pinfunction "VCC_14") (pintype "power_in"))
      (node (ref "IC3") (pin "14") (pinfunction "VCC_14") (pintype "power_in"))
      (node (ref "IC4") (pin "16") (pinfunction "VCC_16") (pintype "power_in"))
      (node (ref "IC6") (pin "10") (pinfunction "ENT_10") (pintype "input"))
      (node (ref "IC6") (pin "7") (pinfunction "ENP_7") (pintype "input"))
      (node (ref "IC8") (pin "14") (pinfunction "VCC_14") (pintype "power_in"))
    )
    (net (code "92") (name "unconnected-(IC1A-CLK-Pad3)") (class "Default")
      (node (ref "IC1") (pin "3") (pinfunction "CLK_3") (pintype "input"))
    )
    (net (code "93") (name "unconnected-(IC1A-D-Pad2)") (class "Default")
      (node (ref "IC1") (pin "2") (pinfunction "D_2") (pintype "input"))
    )
    (net (code "94") (name "unconnected-(IC1A-Q-Pad5)") (class "Default")
      (node (ref "IC1") (pin "5") (pinfunction "Q_5") (pintype "output"))
    )
    (net (code "95") (name "unconnected-(IC1B-CLK-Pad11)") (class "Default")
      (node (ref "IC1") (pin "11") (pinfunction "CLK_11") (pintype "input"))
    )
    (net (code "96") (name "unconnected-(IC1B-D-Pad12)") (class "Default")
      (node (ref "IC1") (pin "12") (pinfunction "D_12") (pintype "input"))
    )
    (net (code "97") (name "unconnected-(IC1B-Q-Pad9)") (class "Default")
      (node (ref "IC1") (pin "9") (pinfunction "Q_9") (pintype "output"))
    )
    (net (code "98") (name "unconnected-(IC2A-CLK-Pad3)") (class "Default")
      (node (ref "IC2") (pin "3") (pinfunction "CLK_3") (pintype "input"))
    )
    (net (code "99") (name "unconnected-(IC2A-D-Pad2)") (class "Default")
      (node (ref "IC2") (pin "2") (pinfunction "D_2") (pintype "input"))
    )
    (net (code "100") (name "unconnected-(IC2A-Q-Pad5)") (class "Default")
      (node (ref "IC2") (pin "5") (pinfunction "Q_5") (pintype "output"))
    )
    (net (code "101") (name "unconnected-(IC2B-CLK-Pad11)") (class "Default")
      (node (ref "IC2") (pin "11") (pinfunction "CLK_11") (pintype "input"))
    )
    (net (code "102") (name "unconnected-(IC2B-D-Pad12)") (class "Default")
      (node (ref "IC2") (pin "12") (pinfunction "D_12") (pintype "input"))
    )
    (net (code "103") (name "unconnected-(IC2B-Q-Pad9)") (class "Default")
      (node (ref "IC2") (pin "9") (pinfunction "Q_9") (pintype "output"))
    )
    (net (code "104") (name "unconnected-(IC4A-CLR-Pad1)") (class "Default")
      (node (ref "IC4") (pin "1") (pinfunction "CLR_1") (pintype "input"))
    )
    (net (code "105") (name "unconnected-(IC4A-LD-Pad9)") (class "Default")
      (node (ref "IC4") (pin "9") (pinfunction "LD_9") (pintype "input"))
    )
    (net (code "106") (name "unconnected-(IC4A-RCO-Pad15)") (class "Default")
      (node (ref "IC4") (pin "15") (pinfunction "RCO_15") (pintype "output"))
    )
    (net (code "107") (name "unconnected-(IC5A-CLR-Pad1)") (class "Default")
      (node (ref "IC5") (pin "1") (pinfunction "CLR_1") (pintype "input"))
    )
    (net (code "108") (name "unconnected-(IC5A-ENP-Pad7)") (class "Default")
      (node (ref "IC5") (pin "7") (pinfunction "ENP_7") (pintype "input"))
    )
    (net (code "109") (name "unconnected-(IC5A-ENT-Pad10)") (class "Default")
      (node (ref "IC5") (pin "10") (pinfunction "ENT_10") (pintype "input"))
    )
    (net (code "110") (name "unconnected-(IC5A-LD-Pad9)") (class "Default")
      (node (ref "IC5") (pin "9") (pinfunction "LD_9") (pintype "input"))
    )
    (net (code "111") (name "unconnected-(IC5A-RCO-Pad15)") (class "Default")
      (node (ref "IC5") (pin "15") (pinfunction "RCO_15") (pintype "output"))
    )
    (net (code "112") (name "unconnected-(IC6A-CLR-Pad1)") (class "Default")
      (node (ref "IC6") (pin "1") (pinfunction "CLR_1") (pintype "input"))
    )
    (net (code "113") (name "unconnected-(IC6A-LD-Pad9)") (class "Default")
      (node (ref "IC6") (pin "9") (pinfunction "LD_9") (pintype "input"))
    )
    (net (code "114") (name "unconnected-(IC6A-RCO-Pad15)") (class "Default")
      (node (ref "IC6") (pin "15") (pinfunction "RCO_15") (pintype "output"))
    )
    (net (code "115") (name "unconnected-(IC7A-CLR-Pad1)") (class "Default")
      (node (ref "IC7") (pin "1") (pinfunction "CLR_1") (pintype "input"))
    )
    (net (code "116") (name "unconnected-(IC7A-LD-Pad9)") (class "Default")
      (node (ref "IC7") (pin "9") (pinfunction "LD_9") (pintype "input"))
    )
    (net (code "117") (name "unconnected-(IC7A-RCO-Pad15)") (class "Default")
      (node (ref "IC7") (pin "15") (pinfunction "RCO_15") (pintype "output"))
    )
    (net (code "118") (name "unconnected-(IC8A-CLK-Pad3)") (class "Default")
      (node (ref "IC8") (pin "3") (pinfunction "CLK_3") (pintype "input"))
    )
    (net (code "119") (name "unconnected-(IC8A-D-Pad2)") (class "Default")
      (node (ref "IC8") (pin "2") (pinfunction "D_2") (pintype "input"))
    )
    (net (code "120") (name "unconnected-(IC8A-Q-Pad5)") (class "Default")
      (node (ref "IC8") (pin "5") (pinfunction "Q_5") (pintype "output"))
    )
    (net (code "121") (name "unconnected-(IC8B-CLK-Pad11)") (class "Default")
      (node (ref "IC8") (pin "11") (pinfunction "CLK_11") (pintype "input"))
    )
    (net (code "122") (name "unconnected-(IC8B-D-Pad12)") (class "Default")
      (node (ref "IC8") (pin "12") (pinfunction "D_12") (pintype "input"))
    )
    (net (code "123") (name "unconnected-(IC8B-Q-Pad9)") (class "Default")
      (node (ref "IC8") (pin "9") (pinfunction "Q_9") (pintype "output"))
    )
    (net (code "124") (name "unconnected-(IC9A-A<B_I-Pad2)") (class "Default")
      (node (ref "IC9") (pin "2") (pinfunction "A<B_I_2") (pintype "input"))
    )
    (net (code "125") (name "unconnected-(IC9A-A=B_I-Pad3)") (class "Default")
      (node (ref "IC9") (pin "3") (pinfunction "A=B_I_3") (pintype "input"))
    )
    (net (code "126") (name "unconnected-(IC9A-A>B_I-Pad4)") (class "Default")
      (node (ref "IC9") (pin "4") (pinfunction "A>B_I_4") (pintype "input"))
    )
    (net (code "127") (name "unconnected-(IC10A-A<B_I-Pad2)") (class "Default")
      (node (ref "IC10") (pin "2") (pinfunction "A<B_I_2") (pintype "input"))
    )
    (net (code "128") (name "unconnected-(IC10A-A=B_I-Pad3)") (class "Default")
      (node (ref "IC10") (pin "3") (pinfunction "A=B_I_3") (pintype "input"))
    )
    (net (code "129") (name "unconnected-(IC10A-A>B_I-Pad4)") (class "Default")
      (node (ref "IC10") (pin "4") (pinfunction "A>B_I_4") (pintype "input"))
    )
    (net (code "130") (name "unconnected-(IC11A-A<B_I-Pad2)") (class "Default")
      (node (ref "IC11") (pin "2") (pinfunction "A<B_I_2") (pintype "input"))
    )
    (net (code "131") (name "unconnected-(IC11A-A=B_I-Pad3)") (class "Default")
      (node (ref "IC11") (pin "3") (pinfunction "A=B_I_3") (pintype "input"))
    )
    (net (code "132") (name "unconnected-(IC11A-A>B_I-Pad4)") (class "Default")
      (node (ref "IC11") (pin "4") (pinfunction "A>B_I_4") (pintype "input"))
    )
    (net (code "133") (name "unconnected-(IC23A-O-Pad3)") (class "Default")
      (node (ref "IC23") (pin "3") (pinfunction "O_3") (pintype "output"))
    )
    (net (code "134") (name "unconnected-(IC24A-1A-Pad3)") (class "Default")
      (node (ref "IC24") (pin "3") (pinfunction "1A_3") (pintype "input"))
    )
    (net (code "135") (name "unconnected-(IC24A-1B-Pad4)") (class "Default")
      (node (ref "IC24") (pin "4") (pinfunction "1B_4") (pintype "input"))
    )
    (net (code "136") (name "unconnected-(IC24A-1Y-Pad5)") (class "Default")
      (node (ref "IC24") (pin "5") (pinfunction "1Y_5") (pintype "output"))
    )
    (net (code "137") (name "unconnected-(IC24A-2A-Pad7)") (class "Default")
      (node (ref "IC24") (pin "7") (pinfunction "2A_7") (pintype "input"))
    )
    (net (code "138") (name "unconnected-(IC24A-2B-Pad8)") (class "Default")
      (node (ref "IC24") (pin "8") (pinfunction "2B_8") (pintype "input"))
    )
    (net (code "139") (name "unconnected-(IC24A-2Y-Pad9)") (class "Default")
      (node (ref "IC24") (pin "9") (pinfunction "2Y_9") (pintype "output"))
    )
    (net (code "140") (name "unconnected-(IC24A-3A-Pad14)") (class "Default")
      (node (ref "IC24") (pin "14") (pinfunction "3A_14") (pintype "input"))
    )
    (net (code "141") (name "unconnected-(IC24A-3B-Pad13)") (class "Default")
      (node (ref "IC24") (pin "13") (pinfunction "3B_13") (pintype "input"))
    )
    (net (code "142") (name "unconnected-(IC24A-3Y-Pad12)") (class "Default")
      (node (ref "IC24") (pin "12") (pinfunction "3Y_12") (pintype "output"))
    )
    (net (code "143") (name "unconnected-(IC24A-4A-Pad18)") (class "Default")
      (node (ref "IC24") (pin "18") (pinfunction "4A_18") (pintype "input"))
    )
    (net (code "144") (name "unconnected-(IC24A-4B-Pad17)") (class "Default")
      (node (ref "IC24") (pin "17") (pinfunction "4B_17") (pintype "input"))
    )
    (net (code "145") (name "unconnected-(IC24A-4Y-Pad15)") (class "Default")
      (node (ref "IC24") (pin "15") (pinfunction "4Y_15") (pintype "output"))
    )
    (net (code "146") (name "unconnected-(IC24A-G-Pad19)") (class "Default")
      (node (ref "IC24") (pin "19") (pinfunction "G_19") (pintype "input"))
    )
    (net (code "147") (name "unconnected-(IC24A-~{A}{slash}B-Pad2)") (class "Default")
      (node (ref "IC24") (pin "2") (pinfunction "~{A}/B_2") (pintype "input"))
    )
    (net (code "148") (name "unconnected-(IC25A-1A-Pad3)") (class "Default")
      (node (ref "IC25") (pin "3") (pinfunction "1A_3") (pintype "input"))
    )
    (net (code "149") (name "unconnected-(IC25A-1B-Pad4)") (class "Default")
      (node (ref "IC25") (pin "4") (pinfunction "1B_4") (pintype "input"))
    )
    (net (code "150") (name "unconnected-(IC25A-1Y-Pad5)") (class "Default")
      (node (ref "IC25") (pin "5") (pinfunction "1Y_5") (pintype "output"))
    )
    (net (code "151") (name "unconnected-(IC25A-2A-Pad7)") (class "Default")
      (node (ref "IC25") (pin "7") (pinfunction "2A_7") (pintype "input"))
    )
    (net (code "152") (name "unconnected-(IC25A-2B-Pad8)") (class "Default")
      (node (ref "IC25") (pin "8") (pinfunction "2B_8") (pintype "input"))
    )
    (net (code "153") (name "unconnected-(IC25A-2Y-Pad9)") (class "Default")
      (node (ref "IC25") (pin "9") (pinfunction "2Y_9") (pintype "output"))
    )
    (net (code "154") (name "unconnected-(IC25A-3A-Pad14)") (class "Default")
      (node (ref "IC25") (pin "14") (pinfunction "3A_14") (pintype "input"))
    )
    (net (code "155") (name "unconnected-(IC25A-3B-Pad13)") (class "Default")
      (node (ref "IC25") (pin "13") (pinfunction "3B_13") (pintype "input"))
    )
    (net (code "156") (name "unconnected-(IC25A-3Y-Pad12)") (class "Default")
      (node (ref "IC25") (pin "12") (pinfunction "3Y_12") (pintype "output"))
    )
    (net (code "157") (name "unconnected-(IC25A-4A-Pad18)") (class "Default")
      (node (ref "IC25") (pin "18") (pinfunction "4A_18") (pintype "input"))
    )
    (net (code "158") (name "unconnected-(IC25A-4B-Pad17)") (class "Default")
      (node (ref "IC25") (pin "17") (pinfunction "4B_17") (pintype "input"))
    )
    (net (code "159") (name "unconnected-(IC25A-4Y-Pad15)") (class "Default")
      (node (ref "IC25") (pin "15") (pinfunction "4Y_15") (pintype "output"))
    )
    (net (code "160") (name "unconnected-(IC25A-G-Pad19)") (class "Default")
      (node (ref "IC25") (pin "19") (pinfunction "G_19") (pintype "input"))
    )
    (net (code "161") (name "unconnected-(IC25A-~{A}{slash}B-Pad2)") (class "Default")
      (node (ref "IC25") (pin "2") (pinfunction "~{A}/B_2") (pintype "input"))
    )
    (net (code "162") (name "unconnected-(SV1-Pad7)") (class "Default")
      (node (ref "SV1") (pin "7") (pinfunction "7_7") (pintype "passive"))
    )
  )
)
